# CPU68K8.net
KiCad netlist of a schematic drawn in EAGLE
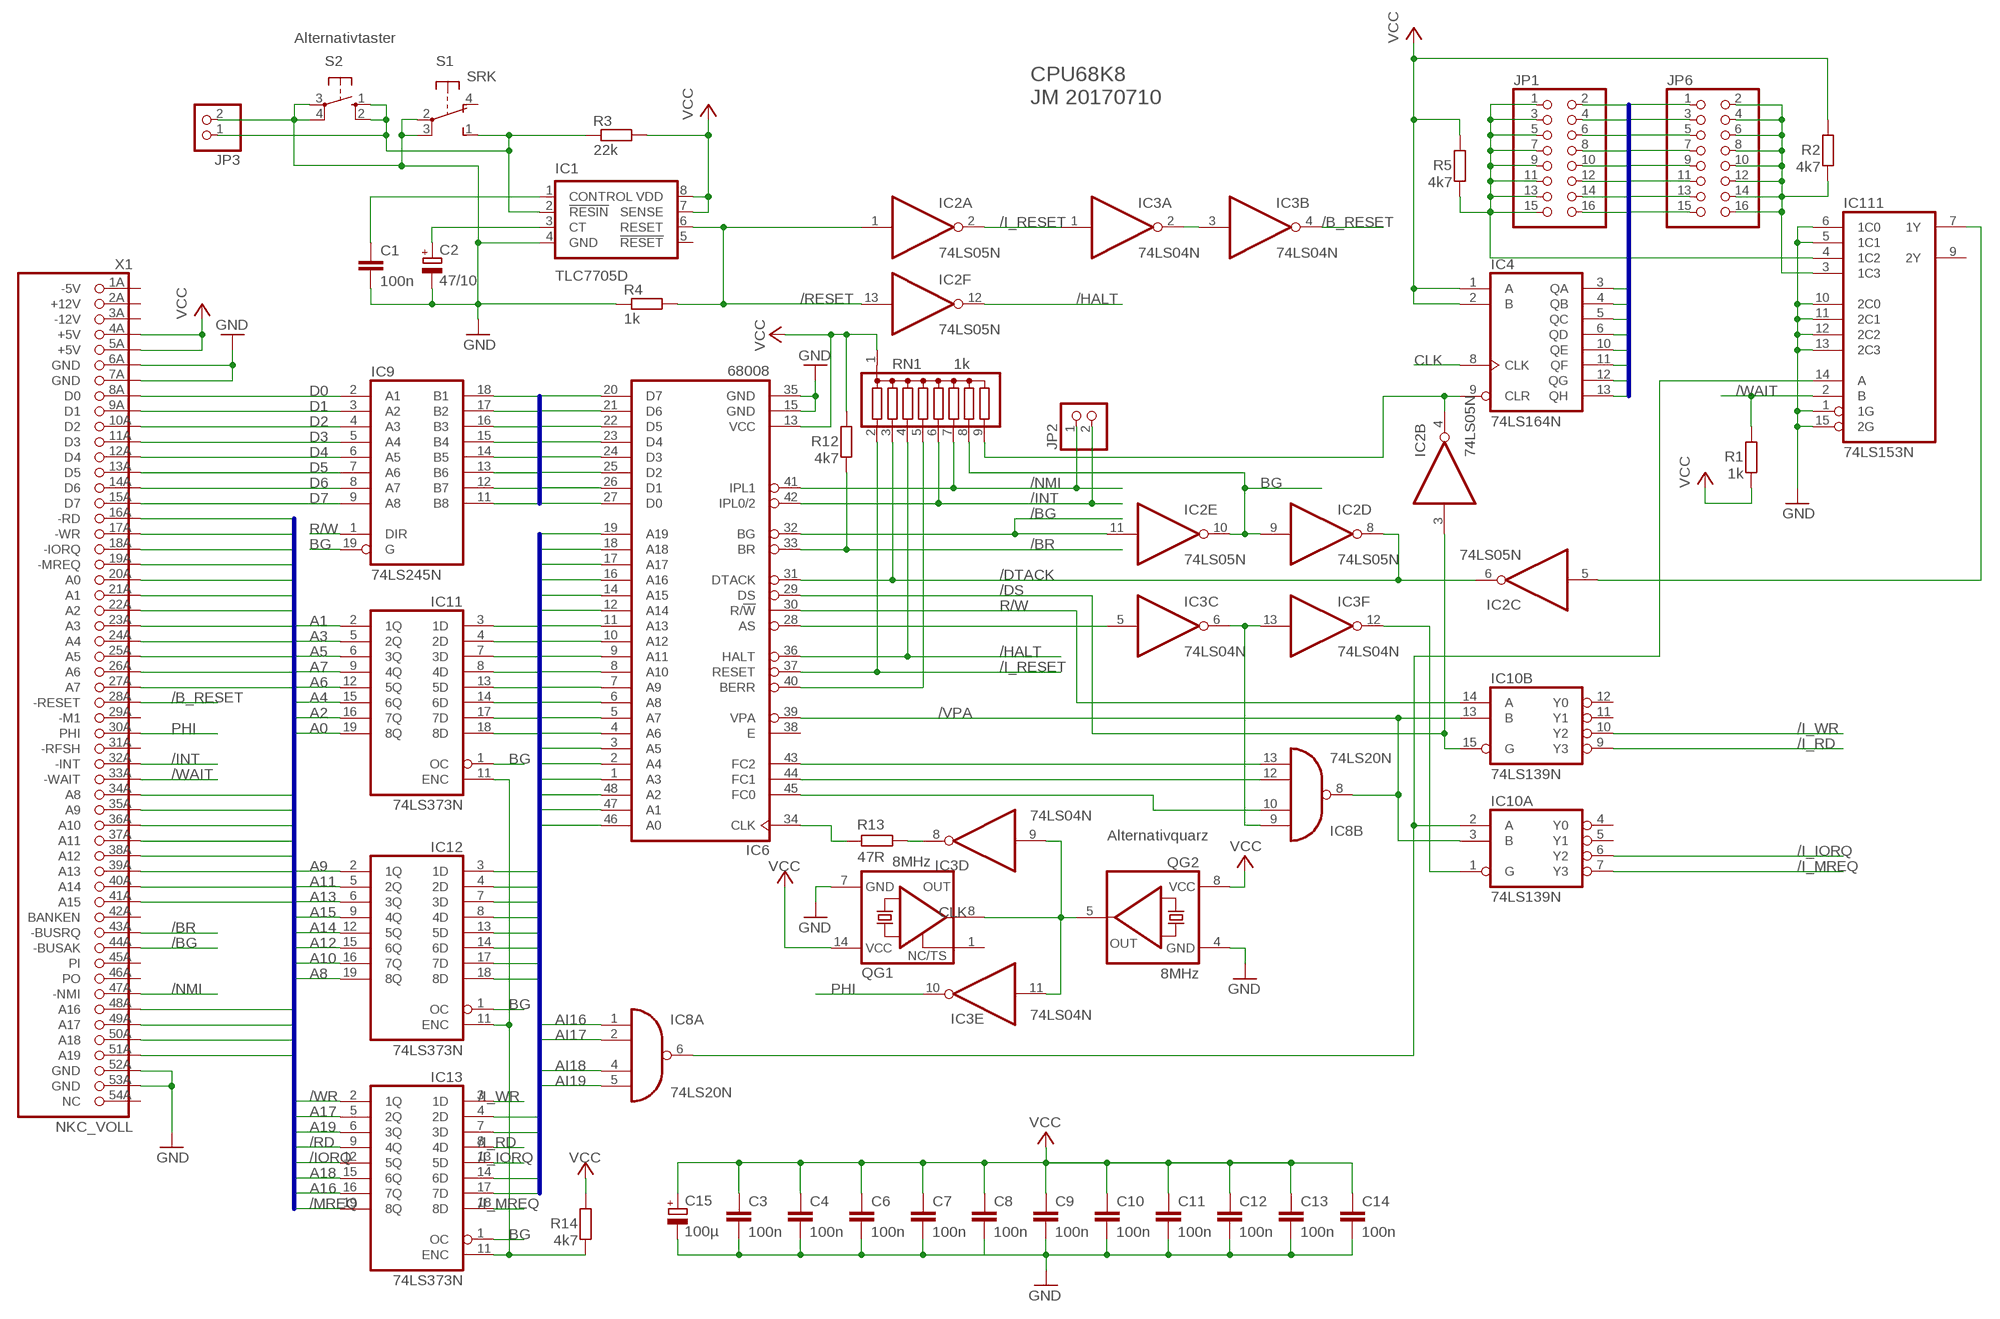
[diagram p0: schematic, sheet 1]

(export (version "E")
  (design (tool "Eeschema 10.0.6"))
  (components
    (comp (ref "C1")
      (value "100n")
      (footprint "eagle-import:C025-025X050")
      (libsource (lib "eagle-import") (part "C-EU025-025X050"))
    )
    (comp (ref "C2")
      (value "47/10")
      (footprint "eagle-import:E2,5-6")
      (libsource (lib "eagle-import") (part "CPOL-EUE2.5-6"))
    )
    (comp (ref "C3")
      (value "100n")
      (footprint "eagle-import:C025-025X050")
      (libsource (lib "eagle-import") (part "C-EU025-025X050"))
    )
    (comp (ref "C4")
      (value "100n")
      (footprint "eagle-import:C025-025X050")
      (libsource (lib "eagle-import") (part "C-EU025-025X050"))
    )
    (comp (ref "C6")
      (value "100n")
      (footprint "eagle-import:C025-025X050")
      (libsource (lib "eagle-import") (part "C-EU025-025X050"))
    )
    (comp (ref "C7")
      (value "100n")
      (footprint "eagle-import:C025-025X050")
      (libsource (lib "eagle-import") (part "C-EU025-025X050"))
    )
    (comp (ref "C8")
      (value "100n")
      (footprint "eagle-import:C025-025X050")
      (libsource (lib "eagle-import") (part "C-EU025-025X050"))
    )
    (comp (ref "C9")
      (value "100n")
      (footprint "eagle-import:C025-025X050")
      (libsource (lib "eagle-import") (part "C-EU025-025X050"))
    )
    (comp (ref "C10")
      (value "100n")
      (footprint "eagle-import:C025-025X050")
      (libsource (lib "eagle-import") (part "C-EU025-025X050"))
    )
    (comp (ref "C11")
      (value "100n")
      (footprint "eagle-import:C025-025X050")
      (libsource (lib "eagle-import") (part "C-EU025-025X050"))
    )
    (comp (ref "C12")
      (value "100n")
      (footprint "eagle-import:C025-025X050")
      (libsource (lib "eagle-import") (part "C-EU025-025X050"))
    )
    (comp (ref "C13")
      (value "100n")
      (footprint "eagle-import:C025-025X050")
      (libsource (lib "eagle-import") (part "C-EU025-025X050"))
    )
    (comp (ref "C14")
      (value "100n")
      (footprint "eagle-import:C025-025X050")
      (libsource (lib "eagle-import") (part "C-EU025-025X050"))
    )
    (comp (ref "C15")
      (value "100µ")
      (footprint "eagle-import:E2,5-6")
      (libsource (lib "eagle-import") (part "CPOL-EUE2.5-6"))
    )
    (comp (ref "IC1")
      (value "TLC7705D")
      (footprint "eagle-import:DIL08")
      (fields (field (name "MF") "TEXAS INSTRUMENT CONNECTORS") (field (name "MPN") "TLC7705QP"))
      (libsource (lib "eagle-import") (part "TLC77D05"))
    )
    (comp (ref "IC2")
      (value "74LS05N")
      (footprint "eagle-import:DIL14")
      (libsource (lib "eagle-import") (part "7405NLS"))
    )
    (comp (ref "IC3")
      (value "74LS04N")
      (footprint "eagle-import:DIL14")
      (libsource (lib "eagle-import") (part "7404NLS"))
    )
    (comp (ref "IC4")
      (value "74LS164N")
      (footprint "eagle-import:DIL14")
      (libsource (lib "eagle-import") (part "74164NLS"))
    )
    (comp (ref "IC6")
      (value "68008")
      (footprint "eagle-import:DIL48")
      (libsource (lib "eagle-import") (part "MC68008P"))
    )
    (comp (ref "IC8")
      (value "74LS20N")
      (footprint "eagle-import:DIL14")
      (libsource (lib "eagle-import") (part "7420NLS"))
    )
    (comp (ref "IC9")
      (value "74LS245N")
      (footprint "eagle-import:DIL20")
      (libsource (lib "eagle-import") (part "74245NLS"))
    )
    (comp (ref "IC10")
      (value "74LS139N")
      (footprint "eagle-import:DIL16")
      (libsource (lib "eagle-import") (part "74139NLS"))
    )
    (comp (ref "IC11")
      (value "74LS373N")
      (footprint "eagle-import:DIL20")
      (libsource (lib "eagle-import") (part "74373NLS"))
    )
    (comp (ref "IC12")
      (value "74LS373N")
      (footprint "eagle-import:DIL20")
      (libsource (lib "eagle-import") (part "74373NLS"))
    )
    (comp (ref "IC13")
      (value "74LS373N")
      (footprint "eagle-import:DIL20")
      (libsource (lib "eagle-import") (part "74373NLS"))
    )
    (comp (ref "IC111")
      (value "74LS153N")
      (footprint "eagle-import:DIL16")
      (libsource (lib "eagle-import") (part "74153NLS"))
    )
    (comp (ref "JP1")
      (value "PINHD-2X8")
      (footprint "eagle-import:2X08")
      (libsource (lib "eagle-import") (part "PINHD-2X8"))
    )
    (comp (ref "JP2")
      (value "PINHD-1X2")
      (footprint "eagle-import:1X02")
      (libsource (lib "eagle-import") (part "PINHD-1X2"))
    )
    (comp (ref "JP3")
      (value "PINHD-1X2/90")
      (footprint "eagle-import:1X02_90")
      (libsource (lib "eagle-import") (part "PINHD-1X2/90"))
    )
    (comp (ref "JP6")
      (value "PINHD-2X8")
      (footprint "eagle-import:2X08")
      (libsource (lib "eagle-import") (part "PINHD-2X8"))
    )
    (comp (ref "QG1")
      (value "8MHz")
      (footprint "eagle-import:DIL14S")
      (libsource (lib "eagle-import") (part "XO-14"))
    )
    (comp (ref "QG2")
      (value "8MHz")
      (footprint "eagle-import:DIL08S")
      (libsource (lib "eagle-import") (part "QG5460"))
    )
    (comp (ref "R1")
      (value "1k")
      (footprint "eagle-import:0207_10")
      (libsource (lib "eagle-import") (part "R-EU_0207/10"))
    )
    (comp (ref "R2")
      (value "4k7")
      (footprint "eagle-import:0207_10")
      (libsource (lib "eagle-import") (part "R-EU_0207/10"))
    )
    (comp (ref "R3")
      (value "22k")
      (footprint "eagle-import:0207_10")
      (libsource (lib "eagle-import") (part "R-EU_0207/10"))
    )
    (comp (ref "R4")
      (value "1k")
      (footprint "eagle-import:0207_10")
      (libsource (lib "eagle-import") (part "R-EU_0207/10"))
    )
    (comp (ref "R5")
      (value "4k7")
      (footprint "eagle-import:0207_10")
      (libsource (lib "eagle-import") (part "R-EU_0207/10"))
    )
    (comp (ref "R12")
      (value "4k7")
      (footprint "eagle-import:0207_10")
      (libsource (lib "eagle-import") (part "R-EU_0207/10"))
    )
    (comp (ref "R13")
      (value "47R")
      (footprint "eagle-import:0207_10")
      (libsource (lib "eagle-import") (part "R-EU_0207/10"))
    )
    (comp (ref "R14")
      (value "4k7")
      (footprint "eagle-import:0207_10")
      (libsource (lib "eagle-import") (part "R-EU_0207/10"))
    )
    (comp (ref "RN1")
      (value "1k")
      (footprint "eagle-import:SIL9")
      (libsource (lib "eagle-import") (part "G08R"))
    )
    (comp (ref "S1")
      (value "SRK")
      (footprint "eagle-import:SRK")
      (libsource (lib "eagle-import") (part "SRK"))
    )
    (comp (ref "S2")
      (value "10-XX")
      (footprint "eagle-import:B3F-10XX")
      (fields (field (name "MPN") "B3F-1000"))
      (libsource (lib "eagle-import") (part "10-XX"))
    )
    (comp (ref "X1")
      (value "NKC_VOLL")
      (footprint "eagle-import:1X54_90_PCB")
      (libsource (lib "eagle-import") (part "NKC_VOLL"))
    )
  )
  (nets
    (net (code "1") (name "/+12V") (class "Default")
      (node (ref "X1") (pin "2A") (pinfunction "+12V_2A") (pintype "power_in"))
    )
    (net (code "2") (name "/-5V") (class "Default")
      (node (ref "X1") (pin "1A") (pinfunction "-5V_1A") (pintype "power_in"))
    )
    (net (code "3") (name "/-12V") (class "Default")
      (node (ref "X1") (pin "3A") (pinfunction "-12V_3A") (pintype "power_in"))
    )
    (net (code "4") (name "/A0") (class "Default")
      (node (ref "IC11") (pin "19") (pinfunction "8Q_19") (pintype "tri_state"))
      (node (ref "X1") (pin "20A") (pinfunction "A0_20A") (pintype "bidirectional"))
    )
    (net (code "5") (name "/A1") (class "Default")
      (node (ref "IC11") (pin "2") (pinfunction "1Q_2") (pintype "tri_state"))
      (node (ref "X1") (pin "21A") (pinfunction "A1_21A") (pintype "bidirectional"))
    )
    (net (code "6") (name "/A2") (class "Default")
      (node (ref "IC11") (pin "16") (pinfunction "7Q_16") (pintype "tri_state"))
      (node (ref "X1") (pin "22A") (pinfunction "A2_22A") (pintype "bidirectional"))
    )
    (net (code "7") (name "/A3") (class "Default")
      (node (ref "IC11") (pin "5") (pinfunction "2Q_5") (pintype "tri_state"))
      (node (ref "X1") (pin "23A") (pinfunction "A3_23A") (pintype "bidirectional"))
    )
    (net (code "8") (name "/A4") (class "Default")
      (node (ref "IC11") (pin "15") (pinfunction "6Q_15") (pintype "tri_state"))
      (node (ref "X1") (pin "24A") (pinfunction "A4_24A") (pintype "bidirectional"))
    )
    (net (code "9") (name "/A5") (class "Default")
      (node (ref "IC11") (pin "6") (pinfunction "3Q_6") (pintype "tri_state"))
      (node (ref "X1") (pin "25A") (pinfunction "A5_25A") (pintype "bidirectional"))
    )
    (net (code "10") (name "/A6") (class "Default")
      (node (ref "IC11") (pin "12") (pinfunction "5Q_12") (pintype "tri_state"))
      (node (ref "X1") (pin "26A") (pinfunction "A6_26A") (pintype "bidirectional"))
    )
    (net (code "11") (name "/A7") (class "Default")
      (node (ref "IC11") (pin "9") (pinfunction "4Q_9") (pintype "tri_state"))
      (node (ref "X1") (pin "27A") (pinfunction "A7_27A") (pintype "bidirectional"))
    )
    (net (code "12") (name "/A8") (class "Default")
      (node (ref "IC12") (pin "19") (pinfunction "8Q_19") (pintype "tri_state"))
      (node (ref "X1") (pin "34A") (pinfunction "A8_34A") (pintype "bidirectional"))
    )
    (net (code "13") (name "/A9") (class "Default")
      (node (ref "IC12") (pin "2") (pinfunction "1Q_2") (pintype "tri_state"))
      (node (ref "X1") (pin "35A") (pinfunction "A9_35A") (pintype "bidirectional"))
    )
    (net (code "14") (name "/A10") (class "Default")
      (node (ref "IC12") (pin "16") (pinfunction "7Q_16") (pintype "tri_state"))
      (node (ref "X1") (pin "36A") (pinfunction "A10_36A") (pintype "bidirectional"))
    )
    (net (code "15") (name "/A11") (class "Default")
      (node (ref "IC12") (pin "5") (pinfunction "2Q_5") (pintype "tri_state"))
      (node (ref "X1") (pin "37A") (pinfunction "A11_37A") (pintype "bidirectional"))
    )
    (net (code "16") (name "/A12") (class "Default")
      (node (ref "IC12") (pin "15") (pinfunction "6Q_15") (pintype "tri_state"))
      (node (ref "X1") (pin "38A") (pinfunction "A12_38A") (pintype "bidirectional"))
    )
    (net (code "17") (name "/A13") (class "Default")
      (node (ref "IC12") (pin "6") (pinfunction "3Q_6") (pintype "tri_state"))
      (node (ref "X1") (pin "39A") (pinfunction "A13_39A") (pintype "bidirectional"))
    )
    (net (code "18") (name "/A14") (class "Default")
      (node (ref "IC12") (pin "12") (pinfunction "5Q_12") (pintype "tri_state"))
      (node (ref "X1") (pin "40A") (pinfunction "A14_40A") (pintype "bidirectional"))
    )
    (net (code "19") (name "/A15") (class "Default")
      (node (ref "IC12") (pin "9") (pinfunction "4Q_9") (pintype "tri_state"))
      (node (ref "X1") (pin "41A") (pinfunction "A15_41A") (pintype "bidirectional"))
    )
    (net (code "20") (name "/A16") (class "Default")
      (node (ref "IC13") (pin "16") (pinfunction "7Q_16") (pintype "tri_state"))
      (node (ref "X1") (pin "48A") (pinfunction "A16_48A") (pintype "bidirectional"))
    )
    (net (code "21") (name "/A17") (class "Default")
      (node (ref "IC13") (pin "5") (pinfunction "2Q_5") (pintype "tri_state"))
      (node (ref "X1") (pin "49A") (pinfunction "A17_49A") (pintype "bidirectional"))
    )
    (net (code "22") (name "/A18") (class "Default")
      (node (ref "IC13") (pin "15") (pinfunction "6Q_15") (pintype "tri_state"))
      (node (ref "X1") (pin "50A") (pinfunction "A18_50A") (pintype "bidirectional"))
    )
    (net (code "23") (name "/A19") (class "Default")
      (node (ref "IC13") (pin "6") (pinfunction "3Q_6") (pintype "tri_state"))
      (node (ref "X1") (pin "51A") (pinfunction "A19_51A") (pintype "bidirectional"))
    )
    (net (code "24") (name "/AI0") (class "Default")
      (node (ref "IC11") (pin "18") (pinfunction "8D_18") (pintype "input"))
      (node (ref "IC6") (pin "46") (pinfunction "A0_46") (pintype "output"))
    )
    (net (code "25") (name "/AI1") (class "Default")
      (node (ref "IC11") (pin "3") (pinfunction "1D_3") (pintype "input"))
      (node (ref "IC6") (pin "47") (pinfunction "A1_47") (pintype "output"))
    )
    (net (code "26") (name "/AI2") (class "Default")
      (node (ref "IC11") (pin "17") (pinfunction "7D_17") (pintype "input"))
      (node (ref "IC6") (pin "48") (pinfunction "A2_48") (pintype "output"))
    )
    (net (code "27") (name "/AI3") (class "Default")
      (node (ref "IC11") (pin "4") (pinfunction "2D_4") (pintype "input"))
      (node (ref "IC6") (pin "1") (pinfunction "A3_1") (pintype "output"))
    )
    (net (code "28") (name "/AI4") (class "Default")
      (node (ref "IC11") (pin "14") (pinfunction "6D_14") (pintype "input"))
      (node (ref "IC6") (pin "2") (pinfunction "A4_2") (pintype "output"))
    )
    (net (code "29") (name "/AI5") (class "Default")
      (node (ref "IC11") (pin "7") (pinfunction "3D_7") (pintype "input"))
      (node (ref "IC6") (pin "3") (pinfunction "A5_3") (pintype "output"))
    )
    (net (code "30") (name "/AI6") (class "Default")
      (node (ref "IC11") (pin "13") (pinfunction "5D_13") (pintype "input"))
      (node (ref "IC6") (pin "4") (pinfunction "A6_4") (pintype "output"))
    )
    (net (code "31") (name "/AI7") (class "Default")
      (node (ref "IC11") (pin "8") (pinfunction "4D_8") (pintype "input"))
      (node (ref "IC6") (pin "5") (pinfunction "A7_5") (pintype "output"))
    )
    (net (code "32") (name "/AI8") (class "Default")
      (node (ref "IC12") (pin "18") (pinfunction "8D_18") (pintype "input"))
      (node (ref "IC6") (pin "6") (pinfunction "A8_6") (pintype "output"))
    )
    (net (code "33") (name "/AI9") (class "Default")
      (node (ref "IC12") (pin "3") (pinfunction "1D_3") (pintype "input"))
      (node (ref "IC6") (pin "7") (pinfunction "A9_7") (pintype "output"))
    )
    (net (code "34") (name "/AI10") (class "Default")
      (node (ref "IC12") (pin "17") (pinfunction "7D_17") (pintype "input"))
      (node (ref "IC6") (pin "8") (pinfunction "A10_8") (pintype "output"))
    )
    (net (code "35") (name "/AI11") (class "Default")
      (node (ref "IC12") (pin "4") (pinfunction "2D_4") (pintype "input"))
      (node (ref "IC6") (pin "9") (pinfunction "A11_9") (pintype "output"))
    )
    (net (code "36") (name "/AI12") (class "Default")
      (node (ref "IC12") (pin "14") (pinfunction "6D_14") (pintype "input"))
      (node (ref "IC6") (pin "10") (pinfunction "A12_10") (pintype "output"))
    )
    (net (code "37") (name "/AI13") (class "Default")
      (node (ref "IC12") (pin "7") (pinfunction "3D_7") (pintype "input"))
      (node (ref "IC6") (pin "11") (pinfunction "A13_11") (pintype "output"))
    )
    (net (code "38") (name "/AI14") (class "Default")
      (node (ref "IC12") (pin "13") (pinfunction "5D_13") (pintype "input"))
      (node (ref "IC6") (pin "12") (pinfunction "A14_12") (pintype "output"))
    )
    (net (code "39") (name "/AI15") (class "Default")
      (node (ref "IC12") (pin "8") (pinfunction "4D_8") (pintype "input"))
      (node (ref "IC6") (pin "14") (pinfunction "A15_14") (pintype "output"))
    )
    (net (code "40") (name "/AI16") (class "Default")
      (node (ref "IC13") (pin "17") (pinfunction "7D_17") (pintype "input"))
      (node (ref "IC6") (pin "16") (pinfunction "A16_16") (pintype "output"))
      (node (ref "IC8") (pin "1") (pinfunction "I0_1") (pintype "input"))
    )
    (net (code "41") (name "/AI17") (class "Default")
      (node (ref "IC13") (pin "4") (pinfunction "2D_4") (pintype "input"))
      (node (ref "IC6") (pin "17") (pinfunction "A17_17") (pintype "output"))
      (node (ref "IC8") (pin "2") (pinfunction "I1_2") (pintype "input"))
    )
    (net (code "42") (name "/AI18") (class "Default")
      (node (ref "IC13") (pin "14") (pinfunction "6D_14") (pintype "input"))
      (node (ref "IC6") (pin "18") (pinfunction "A18_18") (pintype "output"))
      (node (ref "IC8") (pin "4") (pinfunction "I2_4") (pintype "input"))
    )
    (net (code "43") (name "/AI19") (class "Default")
      (node (ref "IC13") (pin "7") (pinfunction "3D_7") (pintype "input"))
      (node (ref "IC6") (pin "19") (pinfunction "A19_19") (pintype "output"))
      (node (ref "IC8") (pin "5") (pinfunction "I3_5") (pintype "input"))
    )
    (net (code "44") (name "/BG") (class "Default")
      (node (ref "IC11") (pin "1") (pinfunction "OC_1") (pintype "input"))
      (node (ref "IC12") (pin "1") (pinfunction "OC_1") (pintype "input"))
      (node (ref "IC13") (pin "1") (pinfunction "OC_1") (pintype "input"))
      (node (ref "IC2") (pin "10") (pinfunction "O_10") (pintype "open_collector"))
      (node (ref "IC2") (pin "9") (pinfunction "I_9") (pintype "input"))
      (node (ref "IC9") (pin "19") (pinfunction "G_19") (pintype "input"))
      (node (ref "RN1") (pin "8") (pinfunction "8_8") (pintype "passive"))
    )
    (net (code "45") (name "/CLK") (class "Default")
      (node (ref "IC3") (pin "11") (pinfunction "I_11") (pintype "input"))
      (node (ref "IC3") (pin "9") (pinfunction "I_9") (pintype "input"))
      (node (ref "IC4") (pin "8") (pinfunction "CLK_8") (pintype "input"))
      (node (ref "QG1") (pin "8") (pinfunction "OUT_8") (pintype "output"))
      (node (ref "QG2") (pin "5") (pinfunction "OUT_5") (pintype "output"))
    )
    (net (code "46") (name "/D0") (class "Default")
      (node (ref "IC9") (pin "2") (pinfunction "A1_2") (pintype "bidirectional"))
      (node (ref "X1") (pin "8A") (pinfunction "D0_8A") (pintype "bidirectional"))
    )
    (net (code "47") (name "/D1") (class "Default")
      (node (ref "IC9") (pin "3") (pinfunction "A2_3") (pintype "bidirectional"))
      (node (ref "X1") (pin "9A") (pinfunction "D1_9A") (pintype "bidirectional"))
    )
    (net (code "48") (name "/D2") (class "Default")
      (node (ref "IC9") (pin "4") (pinfunction "A3_4") (pintype "bidirectional"))
      (node (ref "X1") (pin "10A") (pinfunction "D2_10A") (pintype "bidirectional"))
    )
    (net (code "49") (name "/D3") (class "Default")
      (node (ref "IC9") (pin "5") (pinfunction "A4_5") (pintype "bidirectional"))
      (node (ref "X1") (pin "11A") (pinfunction "D3_11A") (pintype "bidirectional"))
    )
    (net (code "50") (name "/D4") (class "Default")
      (node (ref "IC9") (pin "6") (pinfunction "A5_6") (pintype "bidirectional"))
      (node (ref "X1") (pin "12A") (pinfunction "D4_12A") (pintype "bidirectional"))
    )
    (net (code "51") (name "/D5") (class "Default")
      (node (ref "IC9") (pin "7") (pinfunction "A6_7") (pintype "bidirectional"))
      (node (ref "X1") (pin "13A") (pinfunction "D5_13A") (pintype "bidirectional"))
    )
    (net (code "52") (name "/D6") (class "Default")
      (node (ref "IC9") (pin "8") (pinfunction "A7_8") (pintype "bidirectional"))
      (node (ref "X1") (pin "14A") (pinfunction "D6_14A") (pintype "bidirectional"))
    )
    (net (code "53") (name "/D7") (class "Default")
      (node (ref "IC9") (pin "9") (pinfunction "A8_9") (pintype "bidirectional"))
      (node (ref "X1") (pin "15A") (pinfunction "D7_15A") (pintype "bidirectional"))
    )
    (net (code "54") (name "/DI0") (class "Default")
      (node (ref "IC6") (pin "27") (pinfunction "D0_27") (pintype "bidirectional"))
      (node (ref "IC9") (pin "18") (pinfunction "B1_18") (pintype "bidirectional"))
    )
    (net (code "55") (name "/DI1") (class "Default")
      (node (ref "IC6") (pin "26") (pinfunction "D1_26") (pintype "bidirectional"))
      (node (ref "IC9") (pin "17") (pinfunction "B2_17") (pintype "bidirectional"))
    )
    (net (code "56") (name "/DI2") (class "Default")
      (node (ref "IC6") (pin "25") (pinfunction "D2_25") (pintype "bidirectional"))
      (node (ref "IC9") (pin "16") (pinfunction "B3_16") (pintype "bidirectional"))
    )
    (net (code "57") (name "/DI3") (class "Default")
      (node (ref "IC6") (pin "24") (pinfunction "D3_24") (pintype "bidirectional"))
      (node (ref "IC9") (pin "15") (pinfunction "B4_15") (pintype "bidirectional"))
    )
    (net (code "58") (name "/DI4") (class "Default")
      (node (ref "IC6") (pin "23") (pinfunction "D4_23") (pintype "bidirectional"))
      (node (ref "IC9") (pin "14") (pinfunction "B5_14") (pintype "bidirectional"))
    )
    (net (code "59") (name "/DI5") (class "Default")
      (node (ref "IC6") (pin "22") (pinfunction "D5_22") (pintype "bidirectional"))
      (node (ref "IC9") (pin "13") (pinfunction "B6_13") (pintype "bidirectional"))
    )
    (net (code "60") (name "/DI6") (class "Default")
      (node (ref "IC6") (pin "21") (pinfunction "D6_21") (pintype "bidirectional"))
      (node (ref "IC9") (pin "12") (pinfunction "B7_12") (pintype "bidirectional"))
    )
    (net (code "61") (name "/DI7") (class "Default")
      (node (ref "IC6") (pin "20") (pinfunction "D7_20") (pintype "bidirectional"))
      (node (ref "IC9") (pin "11") (pinfunction "B8_11") (pintype "bidirectional"))
    )
    (net (code "62") (name "/PHI") (class "Default")
      (node (ref "IC3") (pin "10") (pinfunction "O_10") (pintype "output"))
      (node (ref "X1") (pin "30A") (pinfunction "PHI_30A") (pintype "bidirectional"))
    )
    (net (code "63") (name "/R{slash}W") (class "Default")
      (node (ref "IC10") (pin "14") (pinfunction "A_14") (pintype "input"))
      (node (ref "IC6") (pin "30") (pinfunction "R/~{W}_30") (pintype "output"))
      (node (ref "IC9") (pin "1") (pinfunction "DIR_1") (pintype "input"))
    )
    (net (code "64") (name "/WAIT1") (class "Default")
      (node (ref "IC4") (pin "3") (pinfunction "QA_3") (pintype "output"))
      (node (ref "JP1") (pin "2") (pinfunction "2_2") (pintype "passive"))
      (node (ref "JP6") (pin "1") (pinfunction "1_1") (pintype "passive"))
    )
    (net (code "65") (name "/WAIT2") (class "Default")
      (node (ref "IC4") (pin "4") (pinfunction "QB_4") (pintype "output"))
      (node (ref "JP1") (pin "4") (pinfunction "4_4") (pintype "passive"))
      (node (ref "JP6") (pin "3") (pinfunction "3_3") (pintype "passive"))
    )
    (net (code "66") (name "/WAIT3") (class "Default")
      (node (ref "IC4") (pin "5") (pinfunction "QC_5") (pintype "output"))
      (node (ref "JP1") (pin "6") (pinfunction "6_6") (pintype "passive"))
      (node (ref "JP6") (pin "5") (pinfunction "5_5") (pintype "passive"))
    )
    (net (code "67") (name "/WAIT4") (class "Default")
      (node (ref "IC4") (pin "6") (pinfunction "QD_6") (pintype "output"))
      (node (ref "JP1") (pin "8") (pinfunction "8_8") (pintype "passive"))
      (node (ref "JP6") (pin "7") (pinfunction "7_7") (pintype "passive"))
    )
    (net (code "68") (name "/WAIT5") (class "Default")
      (node (ref "IC4") (pin "10") (pinfunction "QE_10") (pintype "output"))
      (node (ref "JP1") (pin "10") (pinfunction "10_10") (pintype "passive"))
      (node (ref "JP6") (pin "9") (pinfunction "9_9") (pintype "passive"))
    )
    (net (code "69") (name "/WAIT6") (class "Default")
      (node (ref "IC4") (pin "11") (pinfunction "QF_11") (pintype "output"))
      (node (ref "JP1") (pin "12") (pinfunction "12_12") (pintype "passive"))
      (node (ref "JP6") (pin "11") (pinfunction "11_11") (pintype "passive"))
    )
    (net (code "70") (name "/WAIT7") (class "Default")
      (node (ref "IC4") (pin "12") (pinfunction "QG_12") (pintype "output"))
      (node (ref "JP1") (pin "14") (pinfunction "14_14") (pintype "passive"))
      (node (ref "JP6") (pin "13") (pinfunction "13_13") (pintype "passive"))
    )
    (net (code "71") (name "/WAIT8") (class "Default")
      (node (ref "IC4") (pin "13") (pinfunction "QH_13") (pintype "output"))
      (node (ref "JP1") (pin "16") (pinfunction "16_16") (pintype "passive"))
      (node (ref "JP6") (pin "15") (pinfunction "15_15") (pintype "passive"))
    )
    (net (code "72") (name "/{slash}BG") (class "Default")
      (node (ref "IC2") (pin "11") (pinfunction "I_11") (pintype "input"))
      (node (ref "IC6") (pin "32") (pinfunction "BG_32") (pintype "output"))
      (node (ref "X1") (pin "44A") (pinfunction "-BUSAK_44A") (pintype "bidirectional"))
    )
    (net (code "73") (name "/{slash}BR") (class "Default")
      (node (ref "IC6") (pin "33") (pinfunction "BR_33") (pintype "input"))
      (node (ref "R12") (pin "1") (pinfunction "1_1") (pintype "passive"))
      (node (ref "X1") (pin "43A") (pinfunction "-BUSRQ_43A") (pintype "bidirectional"))
    )
    (net (code "74") (name "/{slash}B_RESET") (class "Default")
      (node (ref "IC3") (pin "4") (pinfunction "O_4") (pintype "output"))
      (node (ref "X1") (pin "28A") (pinfunction "-RESET_28A") (pintype "bidirectional"))
    )
    (net (code "75") (name "/{slash}DS") (class "Default")
      (node (ref "IC10") (pin "15") (pinfunction "G_15") (pintype "input"))
      (node (ref "IC2") (pin "3") (pinfunction "I_3") (pintype "input"))
      (node (ref "IC6") (pin "29") (pinfunction "DS_29") (pintype "output"))
    )
    (net (code "76") (name "/{slash}DTACK") (class "Default")
      (node (ref "IC2") (pin "6") (pinfunction "O_6") (pintype "open_collector"))
      (node (ref "IC2") (pin "8") (pinfunction "O_8") (pintype "open_collector"))
      (node (ref "IC6") (pin "31") (pinfunction "DTACK_31") (pintype "input"))
      (node (ref "RN1") (pin "3") (pinfunction "3_3") (pintype "passive"))
    )
    (net (code "77") (name "/{slash}HALT") (class "Default")
      (node (ref "IC2") (pin "12") (pinfunction "O_12") (pintype "open_collector"))
      (node (ref "IC6") (pin "36") (pinfunction "HALT_36") (pintype "bidirectional"))
      (node (ref "RN1") (pin "4") (pinfunction "4_4") (pintype "passive"))
    )
    (net (code "78") (name "/{slash}INT") (class "Default")
      (node (ref "IC6") (pin "42") (pinfunction "IPL0/2_42") (pintype "input"))
      (node (ref "JP2") (pin "2") (pinfunction "2_2") (pintype "passive"))
      (node (ref "RN1") (pin "6") (pinfunction "6_6") (pintype "passive"))
      (node (ref "X1") (pin "32A") (pinfunction "-INT_32A") (pintype "bidirectional"))
    )
    (net (code "79") (name "/{slash}IORQ") (class "Default")
      (node (ref "IC13") (pin "12") (pinfunction "5Q_12") (pintype "tri_state"))
      (node (ref "X1") (pin "18A") (pinfunction "-IORQ_18A") (pintype "bidirectional"))
    )
    (net (code "80") (name "/{slash}I_IORQ") (class "Default")
      (node (ref "IC10") (pin "6") (pinfunction "Y2_6") (pintype "output"))
      (node (ref "IC13") (pin "13") (pinfunction "5D_13") (pintype "input"))
    )
    (net (code "81") (name "/{slash}I_MREQ") (class "Default")
      (node (ref "IC10") (pin "7") (pinfunction "Y3_7") (pintype "output"))
      (node (ref "IC13") (pin "18") (pinfunction "8D_18") (pintype "input"))
    )
    (net (code "82") (name "/{slash}I_RD") (class "Default")
      (node (ref "IC10") (pin "9") (pinfunction "Y3_9") (pintype "output"))
      (node (ref "IC13") (pin "8") (pinfunction "4D_8") (pintype "input"))
    )
    (net (code "83") (name "/{slash}I_RESET") (class "Default")
      (node (ref "IC2") (pin "2") (pinfunction "O_2") (pintype "open_collector"))
      (node (ref "IC3") (pin "1") (pinfunction "I_1") (pintype "input"))
      (node (ref "IC6") (pin "37") (pinfunction "RESET_37") (pintype "bidirectional"))
      (node (ref "RN1") (pin "2") (pinfunction "2_2") (pintype "passive"))
    )
    (net (code "84") (name "/{slash}I_WR") (class "Default")
      (node (ref "IC10") (pin "10") (pinfunction "Y2_10") (pintype "output"))
      (node (ref "IC13") (pin "3") (pinfunction "1D_3") (pintype "input"))
    )
    (net (code "85") (name "/{slash}MREQ") (class "Default")
      (node (ref "IC13") (pin "19") (pinfunction "8Q_19") (pintype "tri_state"))
      (node (ref "X1") (pin "19A") (pinfunction "-MREQ_19A") (pintype "bidirectional"))
    )
    (net (code "86") (name "/{slash}NMI") (class "Default")
      (node (ref "IC6") (pin "41") (pinfunction "IPL1_41") (pintype "input"))
      (node (ref "JP2") (pin "1") (pinfunction "1_1") (pintype "passive"))
      (node (ref "RN1") (pin "7") (pinfunction "7_7") (pintype "passive"))
      (node (ref "X1") (pin "47A") (pinfunction "-NMI_47A") (pintype "bidirectional"))
    )
    (net (code "87") (name "/{slash}RD") (class "Default")
      (node (ref "IC13") (pin "9") (pinfunction "4Q_9") (pintype "tri_state"))
      (node (ref "X1") (pin "16A") (pinfunction "-RD_16A") (pintype "bidirectional"))
    )
    (net (code "88") (name "/{slash}RESET") (class "Default")
      (node (ref "IC1") (pin "6") (pinfunction "RESET_6") (pintype "output"))
      (node (ref "IC2") (pin "1") (pinfunction "I_1") (pintype "input"))
      (node (ref "IC2") (pin "13") (pinfunction "I_13") (pintype "input"))
      (node (ref "R4") (pin "2") (pinfunction "2_2") (pintype "passive"))
    )
    (net (code "89") (name "/{slash}VPA") (class "Default")
      (node (ref "IC10") (pin "13") (pinfunction "B_13") (pintype "input"))
      (node (ref "IC10") (pin "3") (pinfunction "B_3") (pintype "input"))
      (node (ref "IC6") (pin "39") (pinfunction "VPA_39") (pintype "input"))
      (node (ref "IC8") (pin "8") (pinfunction "O_8") (pintype "output"))
    )
    (net (code "90") (name "/{slash}WAIT") (class "Default")
      (node (ref "IC111") (pin "2") (pinfunction "B_2") (pintype "input"))
      (node (ref "R1") (pin "2") (pinfunction "2_2") (pintype "passive"))
      (node (ref "X1") (pin "33A") (pinfunction "-WAIT_33A") (pintype "bidirectional"))
    )
    (net (code "91") (name "/{slash}WR") (class "Default")
      (node (ref "IC13") (pin "2") (pinfunction "1Q_2") (pintype "tri_state"))
      (node (ref "X1") (pin "17A") (pinfunction "-WR_17A") (pintype "bidirectional"))
    )
    (net (code "92") (name "GND") (class "Default")
      (node (ref "C1") (pin "2") (pinfunction "2_2") (pintype "passive"))
      (node (ref "C10") (pin "2") (pinfunction "2_2") (pintype "passive"))
      (node (ref "C11") (pin "2") (pinfunction "2_2") (pintype "passive"))
      (node (ref "C12") (pin "2") (pinfunction "2_2") (pintype "passive"))
      (node (ref "C13") (pin "2") (pinfunction "2_2") (pintype "passive"))
      (node (ref "C14") (pin "2") (pinfunction "2_2") (pintype "passive"))
      (node (ref "C15") (pin "-") (pinfunction "-_-") (pintype "passive"))
      (node (ref "C2") (pin "-") (pinfunction "-_-") (pintype "passive"))
      (node (ref "C3") (pin "2") (pinfunction "2_2") (pintype "passive"))
      (node (ref "C4") (pin "2") (pinfunction "2_2") (pintype "passive"))
      (node (ref "C6") (pin "2") (pinfunction "2_2") (pintype "passive"))
      (node (ref "C7") (pin "2") (pinfunction "2_2") (pintype "passive"))
      (node (ref "C8") (pin "2") (pinfunction "2_2") (pintype "passive"))
      (node (ref "C9") (pin "2") (pinfunction "2_2") (pintype "passive"))
      (node (ref "IC1") (pin "4") (pinfunction "GND_4") (pintype "power_in"))
      (node (ref "IC111") (pin "1") (pinfunction "1G_1") (pintype "input"))
      (node (ref "IC111") (pin "10") (pinfunction "2C0_10") (pintype "input"))
      (node (ref "IC111") (pin "11") (pinfunction "2C1_11") (pintype "input"))
      (node (ref "IC111") (pin "12") (pinfunction "2C2_12") (pintype "input"))
      (node (ref "IC111") (pin "13") (pinfunction "2C3_13") (pintype "input"))
      (node (ref "IC111") (pin "15") (pinfunction "2G_15") (pintype "input"))
      (node (ref "IC111") (pin "5") (pinfunction "1C1_5") (pintype "input"))
      (node (ref "IC111") (pin "6") (pinfunction "1C0_6") (pintype "input"))
      (node (ref "IC6") (pin "15") (pinfunction "GND_15") (pintype "power_in"))
      (node (ref "IC6") (pin "35") (pinfunction "GND_35") (pintype "power_in"))
      (node (ref "JP3") (pin "2") (pinfunction "2_2") (pintype "passive"))
      (node (ref "QG1") (pin "7") (pinfunction "GND_7") (pintype "power_in"))
      (node (ref "QG2") (pin "4") (pinfunction "GND_4") (pintype "power_in"))
      (node (ref "R4") (pin "1") (pinfunction "1_1") (pintype "passive"))
      (node (ref "S1") (pin "2") (pinfunction "P_2") (pintype "passive"))
      (node (ref "S1") (pin "3") (pinfunction "P_3") (pintype "passive"))
      (node (ref "S2") (pin "3") (pinfunction "P_3") (pintype "passive"))
      (node (ref "S2") (pin "4") (pinfunction "P1_4") (pintype "passive"))
      (node (ref "X1") (pin "52A") (pinfunction "GND_52A") (pintype "power_in"))
      (node (ref "X1") (pin "53A") (pinfunction "GND_53A") (pintype "power_in"))
      (node (ref "X1") (pin "6A") (pinfunction "GND_6A") (pintype "power_in"))
      (node (ref "X1") (pin "7A") (pinfunction "GND_7A") (pintype "power_in"))
    )
    (net (code "93") (name "Net-(IC1-CONTROL)") (class "Default")
      (node (ref "C1") (pin "1") (pinfunction "1_1") (pintype "passive"))
      (node (ref "IC1") (pin "1") (pinfunction "CONTROL_1") (pintype "input"))
    )
    (net (code "94") (name "Net-(IC1-CT)") (class "Default")
      (node (ref "C2") (pin "+") (pinfunction "+_+") (pintype "passive"))
      (node (ref "IC1") (pin "3") (pinfunction "CT_3") (pintype "input"))
    )
    (net (code "95") (name "Net-(IC1-~{RESIN})") (class "Default")
      (node (ref "IC1") (pin "2") (pinfunction "~{RESIN}_2") (pintype "input"))
      (node (ref "JP3") (pin "1") (pinfunction "1_1") (pintype "passive"))
      (node (ref "R3") (pin "1") (pinfunction "1_1") (pintype "passive"))
      (node (ref "S1") (pin "1") (pinfunction "S_1") (pintype "passive"))
      (node (ref "S2") (pin "1") (pinfunction "S_1") (pintype "passive"))
      (node (ref "S2") (pin "2") (pinfunction "S1_2") (pintype "passive"))
    )
    (net (code "96") (name "Net-(IC2B-O)") (class "Default")
      (node (ref "IC2") (pin "4") (pinfunction "O_4") (pintype "open_collector"))
      (node (ref "IC4") (pin "9") (pinfunction "CLR_9") (pintype "input"))
      (node (ref "RN1") (pin "9") (pinfunction "9_9") (pintype "passive"))
    )
    (net (code "97") (name "Net-(IC3A-O)") (class "Default")
      (node (ref "IC3") (pin "2") (pinfunction "O_2") (pintype "output"))
      (node (ref "IC3") (pin "3") (pinfunction "I_3") (pintype "input"))
    )
    (net (code "98") (name "Net-(IC3C-I)") (class "Default")
      (node (ref "IC3") (pin "5") (pinfunction "I_5") (pintype "input"))
      (node (ref "IC6") (pin "28") (pinfunction "AS_28") (pintype "output"))
    )
    (net (code "99") (name "Net-(IC3C-O)") (class "Default")
      (node (ref "IC3") (pin "13") (pinfunction "I_13") (pintype "input"))
      (node (ref "IC3") (pin "6") (pinfunction "O_6") (pintype "output"))
      (node (ref "IC8") (pin "9") (pinfunction "I0_9") (pintype "input"))
    )
    (net (code "100") (name "Net-(IC3D-O)") (class "Default")
      (node (ref "IC3") (pin "8") (pinfunction "O_8") (pintype "output"))
      (node (ref "R13") (pin "1") (pinfunction "1_1") (pintype "passive"))
    )
    (net (code "101") (name "Net-(IC6-BERR)") (class "Default")
      (node (ref "IC6") (pin "40") (pinfunction "BERR_40") (pintype "input"))
      (node (ref "RN1") (pin "5") (pinfunction "5_5") (pintype "passive"))
    )
    (net (code "102") (name "Net-(IC6-CLK)") (class "Default")
      (node (ref "IC6") (pin "34") (pinfunction "CLK_34") (pintype "input"))
      (node (ref "R13") (pin "2") (pinfunction "2_2") (pintype "passive"))
    )
    (net (code "103") (name "Net-(IC6-FC0)") (class "Default")
      (node (ref "IC6") (pin "45") (pinfunction "FC0_45") (pintype "output"))
      (node (ref "IC8") (pin "10") (pinfunction "I1_10") (pintype "input"))
    )
    (net (code "104") (name "Net-(IC6-FC1)") (class "Default")
      (node (ref "IC6") (pin "44") (pinfunction "FC1_44") (pintype "output"))
      (node (ref "IC8") (pin "12") (pinfunction "I2_12") (pintype "input"))
    )
    (net (code "105") (name "Net-(IC6-FC2)") (class "Default")
      (node (ref "IC6") (pin "43") (pinfunction "FC2_43") (pintype "output"))
      (node (ref "IC8") (pin "13") (pinfunction "I3_13") (pintype "input"))
    )
    (net (code "106") (name "Net-(IC10A-A)") (class "Default")
      (node (ref "IC10") (pin "2") (pinfunction "A_2") (pintype "input"))
      (node (ref "IC111") (pin "14") (pinfunction "A_14") (pintype "input"))
      (node (ref "IC8") (pin "6") (pinfunction "O_6") (pintype "output"))
    )
    (net (code "107") (name "Net-(IC10A-G)") (class "Default")
      (node (ref "IC10") (pin "1") (pinfunction "G_1") (pintype "input"))
      (node (ref "IC3") (pin "12") (pinfunction "O_12") (pintype "output"))
    )
    (net (code "108") (name "Net-(IC11A-ENC)") (class "Default")
      (node (ref "IC11") (pin "11") (pinfunction "ENC_11") (pintype "input"))
      (node (ref "IC12") (pin "11") (pinfunction "ENC_11") (pintype "input"))
      (node (ref "IC13") (pin "11") (pinfunction "ENC_11") (pintype "input"))
      (node (ref "R14") (pin "1") (pinfunction "1_1") (pintype "passive"))
    )
    (net (code "109") (name "Net-(IC111A-1C2)") (class "Default")
      (node (ref "IC111") (pin "4") (pinfunction "1C2_4") (pintype "input"))
      (node (ref "JP1") (pin "1") (pinfunction "1_1") (pintype "passive"))
      (node (ref "JP1") (pin "11") (pinfunction "11_11") (pintype "passive"))
      (node (ref "JP1") (pin "13") (pinfunction "13_13") (pintype "passive"))
      (node (ref "JP1") (pin "15") (pinfunction "15_15") (pintype "passive"))
      (node (ref "JP1") (pin "3") (pinfunction "3_3") (pintype "passive"))
      (node (ref "JP1") (pin "5") (pinfunction "5_5") (pintype "passive"))
      (node (ref "JP1") (pin "7") (pinfunction "7_7") (pintype "passive"))
      (node (ref "JP1") (pin "9") (pinfunction "9_9") (pintype "passive"))
      (node (ref "R5") (pin "1") (pinfunction "1_1") (pintype "passive"))
    )
    (net (code "110") (name "Net-(IC111A-1C3)") (class "Default")
      (node (ref "IC111") (pin "3") (pinfunction "1C3_3") (pintype "input"))
      (node (ref "JP6") (pin "10") (pinfunction "10_10") (pintype "passive"))
      (node (ref "JP6") (pin "12") (pinfunction "12_12") (pintype "passive"))
      (node (ref "JP6") (pin "14") (pinfunction "14_14") (pintype "passive"))
      (node (ref "JP6") (pin "16") (pinfunction "16_16") (pintype "passive"))
      (node (ref "JP6") (pin "2") (pinfunction "2_2") (pintype "passive"))
      (node (ref "JP6") (pin "4") (pinfunction "4_4") (pintype "passive"))
      (node (ref "JP6") (pin "6") (pinfunction "6_6") (pintype "passive"))
      (node (ref "JP6") (pin "8") (pinfunction "8_8") (pintype "passive"))
      (node (ref "R2") (pin "1") (pinfunction "1_1") (pintype "passive"))
    )
    (net (code "111") (name "Net-(IC111A-1Y)") (class "Default")
      (node (ref "IC111") (pin "7") (pinfunction "1Y_7") (pintype "output"))
      (node (ref "IC2") (pin "5") (pinfunction "I_5") (pintype "input"))
    )
    (net (code "112") (name "VCC") (class "Default")
      (node (ref "C10") (pin "1") (pinfunction "1_1") (pintype "passive"))
      (node (ref "C11") (pin "1") (pinfunction "1_1") (pintype "passive"))
      (node (ref "C12") (pin "1") (pinfunction "1_1") (pintype "passive"))
      (node (ref "C13") (pin "1") (pinfunction "1_1") (pintype "passive"))
      (node (ref "C14") (pin "1") (pinfunction "1_1") (pintype "passive"))
      (node (ref "C15") (pin "+") (pinfunction "+_+") (pintype "passive"))
      (node (ref "C3") (pin "1") (pinfunction "1_1") (pintype "passive"))
      (node (ref "C4") (pin "1") (pinfunction "1_1") (pintype "passive"))
      (node (ref "C6") (pin "1") (pinfunction "1_1") (pintype "passive"))
      (node (ref "C7") (pin "1") (pinfunction "1_1") (pintype "passive"))
      (node (ref "C8") (pin "1") (pinfunction "1_1") (pintype "passive"))
      (node (ref "C9") (pin "1") (pinfunction "1_1") (pintype "passive"))
      (node (ref "IC1") (pin "7") (pinfunction "SENSE_7") (pintype "input"))
      (node (ref "IC1") (pin "8") (pinfunction "VDD_8") (pintype "power_in"))
      (node (ref "IC4") (pin "1") (pinfunction "A_1") (pintype "input"))
      (node (ref "IC4") (pin "2") (pinfunction "B_2") (pintype "input"))
      (node (ref "IC6") (pin "13") (pinfunction "VCC_13") (pintype "power_in"))
      (node (ref "QG1") (pin "14") (pinfunction "VCC_14") (pintype "power_in"))
      (node (ref "QG2") (pin "8") (pinfunction "VCC_8") (pintype "power_in"))
      (node (ref "R1") (pin "1") (pinfunction "1_1") (pintype "passive"))
      (node (ref "R12") (pin "2") (pinfunction "2_2") (pintype "passive"))
      (node (ref "R14") (pin "2") (pinfunction "2_2") (pintype "passive"))
      (node (ref "R2") (pin "2") (pinfunction "2_2") (pintype "passive"))
      (node (ref "R3") (pin "2") (pinfunction "2_2") (pintype "passive"))
      (node (ref "R5") (pin "2") (pinfunction "2_2") (pintype "passive"))
      (node (ref "RN1") (pin "1") (pinfunction "1_1") (pintype "passive"))
      (node (ref "X1") (pin "4A") (pinfunction "+5V_4A") (pintype "power_in"))
      (node (ref "X1") (pin "5A") (pinfunction "+5V_5A") (pintype "power_in"))
    )
    (net (code "113") (name "unconnected-(IC1-~{RESET}-Pad5)") (class "Default")
      (node (ref "IC1") (pin "5") (pinfunction "~{RESET}_5") (pintype "output"))
    )
    (net (code "114") (name "unconnected-(IC6-E-Pad38)") (class "Default")
      (node (ref "IC6") (pin "38") (pinfunction "E_38") (pintype "output"))
    )
    (net (code "115") (name "unconnected-(IC10A-Y0-Pad4)") (class "Default")
      (node (ref "IC10") (pin "4") (pinfunction "Y0_4") (pintype "output"))
    )
    (net (code "116") (name "unconnected-(IC10A-Y1-Pad5)") (class "Default")
      (node (ref "IC10") (pin "5") (pinfunction "Y1_5") (pintype "output"))
    )
    (net (code "117") (name "unconnected-(IC10B-Y0-Pad12)") (class "Default")
      (node (ref "IC10") (pin "12") (pinfunction "Y0_12") (pintype "output"))
    )
    (net (code "118") (name "unconnected-(IC10B-Y1-Pad11)") (class "Default")
      (node (ref "IC10") (pin "11") (pinfunction "Y1_11") (pintype "output"))
    )
    (net (code "119") (name "unconnected-(IC111A-2Y-Pad9)") (class "Default")
      (node (ref "IC111") (pin "9") (pinfunction "2Y_9") (pintype "output"))
    )
    (net (code "120") (name "unconnected-(QG1-TS-Pad1)") (class "Default")
      (node (ref "QG1") (pin "1") (pinfunction "TS_1") (pintype "passive"))
    )
    (net (code "121") (name "unconnected-(S1-O-Pad4)") (class "Default")
      (node (ref "S1") (pin "4") (pinfunction "O_4") (pintype "passive"))
    )
    (net (code "122") (name "unconnected-(X1--M1-Pad29A)") (class "Default")
      (node (ref "X1") (pin "29A") (pinfunction "-M1_29A") (pintype "bidirectional"))
    )
    (net (code "123") (name "unconnected-(X1--RFSH-Pad31A)") (class "Default")
      (node (ref "X1") (pin "31A") (pinfunction "-RFSH_31A") (pintype "bidirectional"))
    )
    (net (code "124") (name "unconnected-(X1-BANKEN-Pad42A)") (class "Default")
      (node (ref "X1") (pin "42A") (pinfunction "BANKEN_42A") (pintype "bidirectional"))
    )
    (net (code "125") (name "unconnected-(X1-NC-Pad54A)") (class "Default")
      (node (ref "X1") (pin "54A") (pinfunction "NC_54A") (pintype "no_connect"))
    )
    (net (code "126") (name "unconnected-(X1-PI-Pad45A)") (class "Default")
      (node (ref "X1") (pin "45A") (pinfunction "PI_45A") (pintype "bidirectional"))
    )
    (net (code "127") (name "unconnected-(X1-PO-Pad46A)") (class "Default")
      (node (ref "X1") (pin "46A") (pinfunction "PO_46A") (pintype "bidirectional"))
    )
  )
)
